# DCDC_Motherbord.net
KiCad netlist of a schematic drawn in Altium Designer
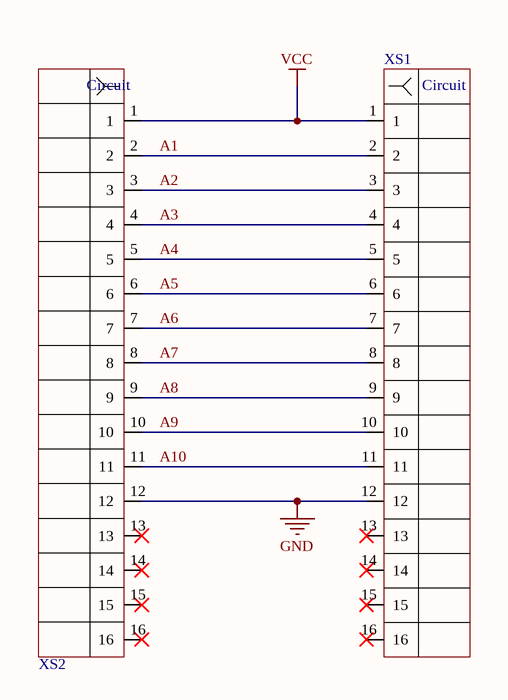
[diagram p0: DCDC_Motherbord.SchDoc]

(export (version "E")
  (design (tool "Eeschema 10.0.6"))
  (components
    (comp (ref "XS1")
      (value "PBD-16")
      (footprint "PBD-16-3D")
      (description "CONN RCPT 16POS 0.1 GOLD PCB")
      (fields (field (name "PART NUMBER") "SH2-16G") (field (name "DIGI-KEY PART NUMBER") "ED3071-ND"))
      (libsource (lib "") (part "XS-16_1"))
    )
    (comp (ref "XS2")
      (value "PBD-16")
      (footprint "PBD-16-3D")
      (description "CONN RCPT 16POS 0.1 GOLD PCB")
      (fields (field (name "PART NUMBER") "SH2-16G") (field (name "DIGI-KEY PART NUMBER") "ED3071-ND"))
      (libsource (lib "SssAccesDatbase") (part "XS-16"))
    )
  )
  (nets
    (net (code "1") (name "/A1") (class "Default")
      (node (ref "XS1") (pin "2") (pinfunction "2_2") (pintype "passive"))
      (node (ref "XS2") (pin "2") (pinfunction "2_2") (pintype "passive"))
    )
    (net (code "2") (name "/A2") (class "Default")
      (node (ref "XS1") (pin "3") (pinfunction "3_3") (pintype "passive"))
      (node (ref "XS2") (pin "3") (pinfunction "3_3") (pintype "passive"))
    )
    (net (code "3") (name "/A3") (class "Default")
      (node (ref "XS1") (pin "4") (pinfunction "4_4") (pintype "passive"))
      (node (ref "XS2") (pin "4") (pinfunction "4_4") (pintype "passive"))
    )
    (net (code "4") (name "/A4") (class "Default")
      (node (ref "XS1") (pin "5") (pinfunction "5_5") (pintype "passive"))
      (node (ref "XS2") (pin "5") (pinfunction "5_5") (pintype "passive"))
    )
    (net (code "5") (name "/A5") (class "Default")
      (node (ref "XS1") (pin "6") (pinfunction "6_6") (pintype "passive"))
      (node (ref "XS2") (pin "6") (pinfunction "6_6") (pintype "passive"))
    )
    (net (code "6") (name "/A6") (class "Default")
      (node (ref "XS1") (pin "7") (pinfunction "7_7") (pintype "passive"))
      (node (ref "XS2") (pin "7") (pinfunction "7_7") (pintype "passive"))
    )
    (net (code "7") (name "/A7") (class "Default")
      (node (ref "XS1") (pin "8") (pinfunction "8_8") (pintype "passive"))
      (node (ref "XS2") (pin "8") (pinfunction "8_8") (pintype "passive"))
    )
    (net (code "8") (name "/A8") (class "Default")
      (node (ref "XS1") (pin "9") (pinfunction "9_9") (pintype "passive"))
      (node (ref "XS2") (pin "9") (pinfunction "9_9") (pintype "passive"))
    )
    (net (code "9") (name "/A9") (class "Default")
      (node (ref "XS1") (pin "10") (pinfunction "10_10") (pintype "passive"))
      (node (ref "XS2") (pin "10") (pinfunction "10_10") (pintype "passive"))
    )
    (net (code "10") (name "/A10") (class "Default")
      (node (ref "XS1") (pin "11") (pinfunction "11_11") (pintype "passive"))
      (node (ref "XS2") (pin "11") (pinfunction "11_11") (pintype "passive"))
    )
    (net (code "11") (name "GND") (class "Default")
      (node (ref "XS1") (pin "12") (pinfunction "12_12") (pintype "passive"))
      (node (ref "XS2") (pin "12") (pinfunction "12_12") (pintype "passive"))
    )
    (net (code "12") (name "VCC") (class "Default")
      (node (ref "XS1") (pin "1") (pinfunction "1_1") (pintype "passive"))
      (node (ref "XS2") (pin "1") (pinfunction "1_1") (pintype "passive"))
    )
    (net (code "13") (name "unconnected-(XS1-Pad13)") (class "Default")
      (node (ref "XS1") (pin "13") (pinfunction "13_13") (pintype "passive+no_connect"))
    )
    (net (code "14") (name "unconnected-(XS1-Pad14)") (class "Default")
      (node (ref "XS1") (pin "14") (pinfunction "14_14") (pintype "passive+no_connect"))
    )
    (net (code "15") (name "unconnected-(XS1-Pad15)") (class "Default")
      (node (ref "XS1") (pin "15") (pinfunction "15_15") (pintype "passive+no_connect"))
    )
    (net (code "16") (name "unconnected-(XS1-Pad16)") (class "Default")
      (node (ref "XS1") (pin "16") (pinfunction "16_16") (pintype "passive+no_connect"))
    )
    (net (code "17") (name "unconnected-(XS2-Pad13)") (class "Default")
      (node (ref "XS2") (pin "13") (pinfunction "13_13") (pintype "passive+no_connect"))
    )
    (net (code "18") (name "unconnected-(XS2-Pad14)") (class "Default")
      (node (ref "XS2") (pin "14") (pinfunction "14_14") (pintype "passive+no_connect"))
    )
    (net (code "19") (name "unconnected-(XS2-Pad15)") (class "Default")
      (node (ref "XS2") (pin "15") (pinfunction "15_15") (pintype "passive+no_connect"))
    )
    (net (code "20") (name "unconnected-(XS2-Pad16)") (class "Default")
      (node (ref "XS2") (pin "16") (pinfunction "16_16") (pintype "passive+no_connect"))
    )
  )
)
